# led-strip-main-connector.net
KiCad netlist of a schematic drawn in EAGLE
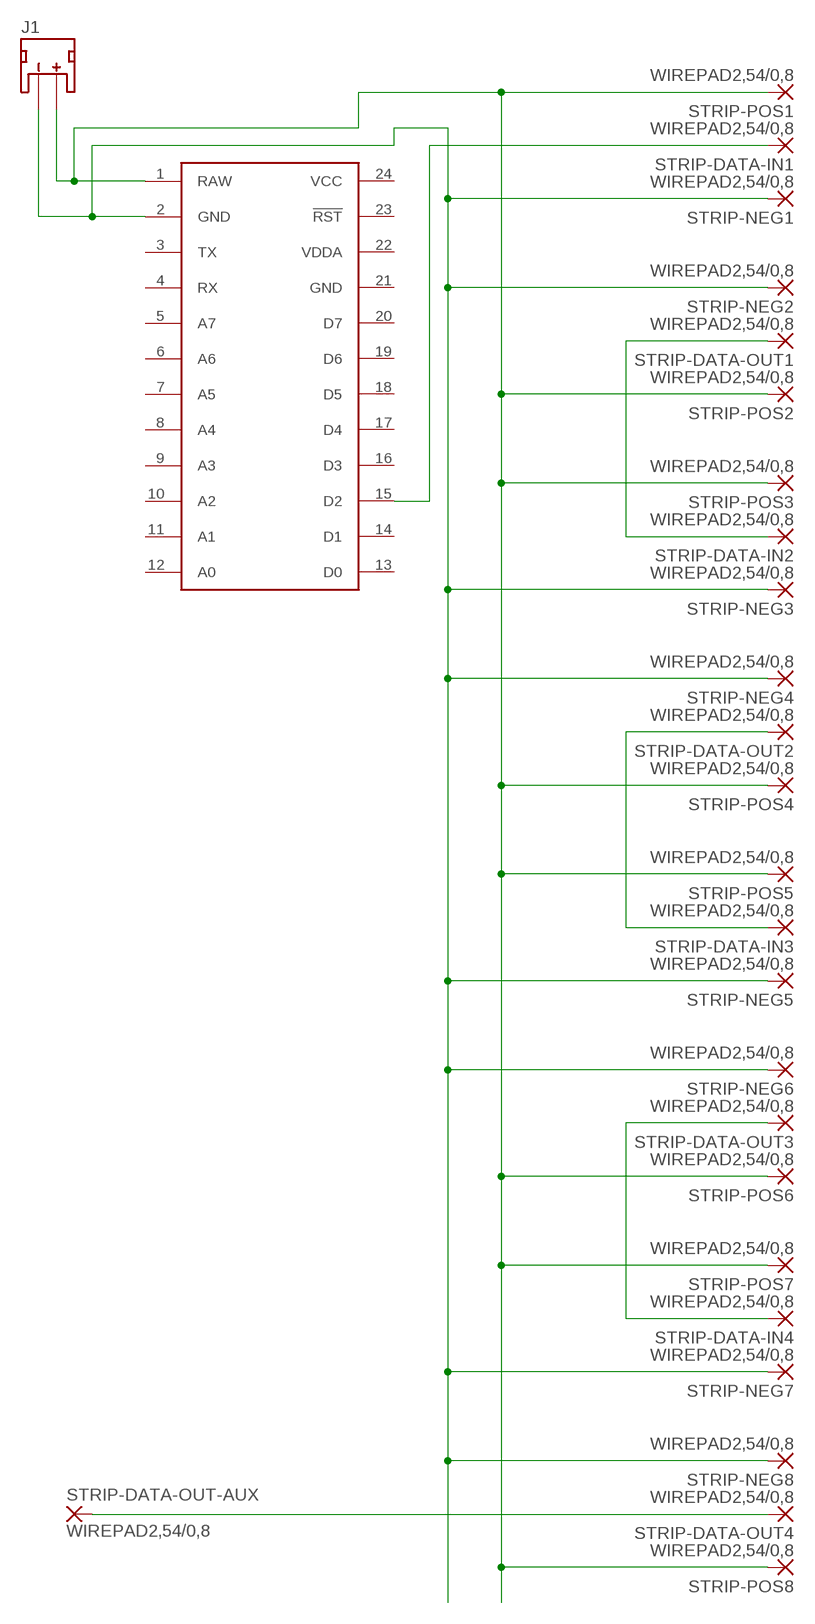
[diagram p0: schematic, sheet 1]

(export (version "E")
  (design (tool "Eeschema 10.0.6"))
  (components
    (comp (ref "J1")
      (value "1")
      (footprint "eagle-import:JST-2-SMD")
      (libsource (lib "eagle-import") (part "JST_2MM_MALE"))
    )
    (comp (ref "SPARK_CORE")
      (value "SPARK_CORECORE")
      (footprint "eagle-import:SPARK_CORE")
      (libsource (lib "eagle-import") (part "SPARK_CORECORE"))
    )
    (comp (ref "STRIP-DATA-IN1")
      (value "WIREPAD2,54/0,8")
      (footprint "eagle-import:2,54_0,8")
      (libsource (lib "eagle-import") (part "WIREPAD2,54/0,8"))
    )
    (comp (ref "STRIP-DATA-IN2")
      (value "WIREPAD2,54/0,8")
      (footprint "eagle-import:2,54_0,8")
      (libsource (lib "eagle-import") (part "WIREPAD2,54/0,8"))
    )
    (comp (ref "STRIP-DATA-IN3")
      (value "WIREPAD2,54/0,8")
      (footprint "eagle-import:2,54_0,8")
      (libsource (lib "eagle-import") (part "WIREPAD2,54/0,8"))
    )
    (comp (ref "STRIP-DATA-IN4")
      (value "WIREPAD2,54/0,8")
      (footprint "eagle-import:2,54_0,8")
      (libsource (lib "eagle-import") (part "WIREPAD2,54/0,8"))
    )
    (comp (ref "STRIP-DATA-OUT-AUX")
      (value "WIREPAD2,54/0,8")
      (footprint "eagle-import:2,54_0,8")
      (libsource (lib "eagle-import") (part "WIREPAD2,54/0,8"))
    )
    (comp (ref "STRIP-DATA-OUT1")
      (value "WIREPAD2,54/0,8")
      (footprint "eagle-import:2,54_0,8")
      (libsource (lib "eagle-import") (part "WIREPAD2,54/0,8"))
    )
    (comp (ref "STRIP-DATA-OUT2")
      (value "WIREPAD2,54/0,8")
      (footprint "eagle-import:2,54_0,8")
      (libsource (lib "eagle-import") (part "WIREPAD2,54/0,8"))
    )
    (comp (ref "STRIP-DATA-OUT3")
      (value "WIREPAD2,54/0,8")
      (footprint "eagle-import:2,54_0,8")
      (libsource (lib "eagle-import") (part "WIREPAD2,54/0,8"))
    )
    (comp (ref "STRIP-DATA-OUT4")
      (value "WIREPAD2,54/0,8")
      (footprint "eagle-import:2,54_0,8")
      (libsource (lib "eagle-import") (part "WIREPAD2,54/0,8"))
    )
    (comp (ref "STRIP-NEG1")
      (value "WIREPAD2,54/0,8")
      (footprint "eagle-import:2,54_0,8")
      (libsource (lib "eagle-import") (part "WIREPAD2,54/0,8"))
    )
    (comp (ref "STRIP-NEG2")
      (value "WIREPAD2,54/0,8")
      (footprint "eagle-import:2,54_0,8")
      (libsource (lib "eagle-import") (part "WIREPAD2,54/0,8"))
    )
    (comp (ref "STRIP-NEG3")
      (value "WIREPAD2,54/0,8")
      (footprint "eagle-import:2,54_0,8")
      (libsource (lib "eagle-import") (part "WIREPAD2,54/0,8"))
    )
    (comp (ref "STRIP-NEG4")
      (value "WIREPAD2,54/0,8")
      (footprint "eagle-import:2,54_0,8")
      (libsource (lib "eagle-import") (part "WIREPAD2,54/0,8"))
    )
    (comp (ref "STRIP-NEG5")
      (value "WIREPAD2,54/0,8")
      (footprint "eagle-import:2,54_0,8")
      (libsource (lib "eagle-import") (part "WIREPAD2,54/0,8"))
    )
    (comp (ref "STRIP-NEG6")
      (value "WIREPAD2,54/0,8")
      (footprint "eagle-import:2,54_0,8")
      (libsource (lib "eagle-import") (part "WIREPAD2,54/0,8"))
    )
    (comp (ref "STRIP-NEG7")
      (value "WIREPAD2,54/0,8")
      (footprint "eagle-import:2,54_0,8")
      (libsource (lib "eagle-import") (part "WIREPAD2,54/0,8"))
    )
    (comp (ref "STRIP-NEG8")
      (value "WIREPAD2,54/0,8")
      (footprint "eagle-import:2,54_0,8")
      (libsource (lib "eagle-import") (part "WIREPAD2,54/0,8"))
    )
    (comp (ref "STRIP-POS1")
      (value "WIREPAD2,54/0,8")
      (footprint "eagle-import:2,54_0,8")
      (libsource (lib "eagle-import") (part "WIREPAD2,54/0,8"))
    )
    (comp (ref "STRIP-POS2")
      (value "WIREPAD2,54/0,8")
      (footprint "eagle-import:2,54_0,8")
      (libsource (lib "eagle-import") (part "WIREPAD2,54/0,8"))
    )
    (comp (ref "STRIP-POS3")
      (value "WIREPAD2,54/0,8")
      (footprint "eagle-import:2,54_0,8")
      (libsource (lib "eagle-import") (part "WIREPAD2,54/0,8"))
    )
    (comp (ref "STRIP-POS4")
      (value "WIREPAD2,54/0,8")
      (footprint "eagle-import:2,54_0,8")
      (libsource (lib "eagle-import") (part "WIREPAD2,54/0,8"))
    )
    (comp (ref "STRIP-POS5")
      (value "WIREPAD2,54/0,8")
      (footprint "eagle-import:2,54_0,8")
      (libsource (lib "eagle-import") (part "WIREPAD2,54/0,8"))
    )
    (comp (ref "STRIP-POS6")
      (value "WIREPAD2,54/0,8")
      (footprint "eagle-import:2,54_0,8")
      (libsource (lib "eagle-import") (part "WIREPAD2,54/0,8"))
    )
    (comp (ref "STRIP-POS7")
      (value "WIREPAD2,54/0,8")
      (footprint "eagle-import:2,54_0,8")
      (libsource (lib "eagle-import") (part "WIREPAD2,54/0,8"))
    )
    (comp (ref "STRIP-POS8")
      (value "WIREPAD2,54/0,8")
      (footprint "eagle-import:2,54_0,8")
      (libsource (lib "eagle-import") (part "WIREPAD2,54/0,8"))
    )
  )
  (nets
    (net (code "1") (name "/GND") (class "Default")
      (node (ref "SPARK_CORE") (pin "21") (pinfunction "GND_21") (pintype "power_in"))
    )
    (net (code "2") (name "/VCC") (class "Default")
      (node (ref "SPARK_CORE") (pin "24") (pinfunction "VCC_24") (pintype "power_in"))
    )
    (net (code "3") (name "/VDDA") (class "Default")
      (node (ref "SPARK_CORE") (pin "22") (pinfunction "VDDA_22") (pintype "power_in"))
    )
    (net (code "4") (name "Net-(J1-+)") (class "Default")
      (node (ref "J1") (pin "2") (pinfunction "+_2") (pintype "bidirectional"))
      (node (ref "SPARK_CORE") (pin "1") (pinfunction "RAW_1") (pintype "power_in"))
      (node (ref "STRIP-POS1") (pin "1") (pinfunction "P_1") (pintype "passive"))
      (node (ref "STRIP-POS2") (pin "1") (pinfunction "P_1") (pintype "passive"))
      (node (ref "STRIP-POS3") (pin "1") (pinfunction "P_1") (pintype "passive"))
      (node (ref "STRIP-POS4") (pin "1") (pinfunction "P_1") (pintype "passive"))
      (node (ref "STRIP-POS5") (pin "1") (pinfunction "P_1") (pintype "passive"))
      (node (ref "STRIP-POS6") (pin "1") (pinfunction "P_1") (pintype "passive"))
      (node (ref "STRIP-POS7") (pin "1") (pinfunction "P_1") (pintype "passive"))
      (node (ref "STRIP-POS8") (pin "1") (pinfunction "P_1") (pintype "passive"))
    )
    (net (code "5") (name "Net-(J1--)") (class "Default")
      (node (ref "J1") (pin "1") (pinfunction "-_1") (pintype "bidirectional"))
      (node (ref "SPARK_CORE") (pin "2") (pinfunction "GND_2") (pintype "power_in"))
      (node (ref "STRIP-NEG1") (pin "1") (pinfunction "P_1") (pintype "passive"))
      (node (ref "STRIP-NEG2") (pin "1") (pinfunction "P_1") (pintype "passive"))
      (node (ref "STRIP-NEG3") (pin "1") (pinfunction "P_1") (pintype "passive"))
      (node (ref "STRIP-NEG4") (pin "1") (pinfunction "P_1") (pintype "passive"))
      (node (ref "STRIP-NEG5") (pin "1") (pinfunction "P_1") (pintype "passive"))
      (node (ref "STRIP-NEG6") (pin "1") (pinfunction "P_1") (pintype "passive"))
      (node (ref "STRIP-NEG7") (pin "1") (pinfunction "P_1") (pintype "passive"))
      (node (ref "STRIP-NEG8") (pin "1") (pinfunction "P_1") (pintype "passive"))
    )
    (net (code "6") (name "Net-(SPARK_CORE-D2)") (class "Default")
      (node (ref "SPARK_CORE") (pin "15") (pinfunction "D2_15") (pintype "bidirectional"))
      (node (ref "STRIP-DATA-IN1") (pin "1") (pinfunction "P_1") (pintype "passive"))
    )
    (net (code "7") (name "Net-(STRIP-DATA-IN2-P)") (class "Default")
      (node (ref "STRIP-DATA-IN2") (pin "1") (pinfunction "P_1") (pintype "passive"))
      (node (ref "STRIP-DATA-OUT1") (pin "1") (pinfunction "P_1") (pintype "passive"))
    )
    (net (code "8") (name "Net-(STRIP-DATA-IN3-P)") (class "Default")
      (node (ref "STRIP-DATA-IN3") (pin "1") (pinfunction "P_1") (pintype "passive"))
      (node (ref "STRIP-DATA-OUT2") (pin "1") (pinfunction "P_1") (pintype "passive"))
    )
    (net (code "9") (name "Net-(STRIP-DATA-IN4-P)") (class "Default")
      (node (ref "STRIP-DATA-IN4") (pin "1") (pinfunction "P_1") (pintype "passive"))
      (node (ref "STRIP-DATA-OUT3") (pin "1") (pinfunction "P_1") (pintype "passive"))
    )
    (net (code "10") (name "Net-(STRIP-DATA-OUT-AUX-P)") (class "Default")
      (node (ref "STRIP-DATA-OUT-AUX") (pin "1") (pinfunction "P_1") (pintype "passive"))
      (node (ref "STRIP-DATA-OUT4") (pin "1") (pinfunction "P_1") (pintype "passive"))
    )
    (net (code "11") (name "unconnected-(J1-PAD1-PadNC1)") (class "Default")
      (node (ref "J1") (pin "NC1") (pinfunction "PAD1_NC1") (pintype "bidirectional"))
    )
    (net (code "12") (name "unconnected-(J1-PAD2-PadNC2)") (class "Default")
      (node (ref "J1") (pin "NC2") (pinfunction "PAD2_NC2") (pintype "bidirectional"))
    )
    (net (code "13") (name "unconnected-(SPARK_CORE-A0-Pad12)") (class "Default")
      (node (ref "SPARK_CORE") (pin "12") (pinfunction "A0_12") (pintype "bidirectional"))
    )
    (net (code "14") (name "unconnected-(SPARK_CORE-A1-Pad11)") (class "Default")
      (node (ref "SPARK_CORE") (pin "11") (pinfunction "A1_11") (pintype "bidirectional"))
    )
    (net (code "15") (name "unconnected-(SPARK_CORE-A2-Pad10)") (class "Default")
      (node (ref "SPARK_CORE") (pin "10") (pinfunction "A2_10") (pintype "bidirectional"))
    )
    (net (code "16") (name "unconnected-(SPARK_CORE-A3-Pad9)") (class "Default")
      (node (ref "SPARK_CORE") (pin "9") (pinfunction "A3_9") (pintype "bidirectional"))
    )
    (net (code "17") (name "unconnected-(SPARK_CORE-A4-Pad8)") (class "Default")
      (node (ref "SPARK_CORE") (pin "8") (pinfunction "A4_8") (pintype "bidirectional"))
    )
    (net (code "18") (name "unconnected-(SPARK_CORE-A5-Pad7)") (class "Default")
      (node (ref "SPARK_CORE") (pin "7") (pinfunction "A5_7") (pintype "bidirectional"))
    )
    (net (code "19") (name "unconnected-(SPARK_CORE-A6-Pad6)") (class "Default")
      (node (ref "SPARK_CORE") (pin "6") (pinfunction "A6_6") (pintype "bidirectional"))
    )
    (net (code "20") (name "unconnected-(SPARK_CORE-A7-Pad5)") (class "Default")
      (node (ref "SPARK_CORE") (pin "5") (pinfunction "A7_5") (pintype "bidirectional"))
    )
    (net (code "21") (name "unconnected-(SPARK_CORE-D0-Pad13)") (class "Default")
      (node (ref "SPARK_CORE") (pin "13") (pinfunction "D0_13") (pintype "bidirectional"))
    )
    (net (code "22") (name "unconnected-(SPARK_CORE-D1-Pad14)") (class "Default")
      (node (ref "SPARK_CORE") (pin "14") (pinfunction "D1_14") (pintype "bidirectional"))
    )
    (net (code "23") (name "unconnected-(SPARK_CORE-D3-Pad16)") (class "Default")
      (node (ref "SPARK_CORE") (pin "16") (pinfunction "D3_16") (pintype "bidirectional"))
    )
    (net (code "24") (name "unconnected-(SPARK_CORE-D4-Pad17)") (class "Default")
      (node (ref "SPARK_CORE") (pin "17") (pinfunction "D4_17") (pintype "bidirectional"))
    )
    (net (code "25") (name "unconnected-(SPARK_CORE-D5-Pad18)") (class "Default")
      (node (ref "SPARK_CORE") (pin "18") (pinfunction "D5_18") (pintype "bidirectional"))
    )
    (net (code "26") (name "unconnected-(SPARK_CORE-D6-Pad19)") (class "Default")
      (node (ref "SPARK_CORE") (pin "19") (pinfunction "D6_19") (pintype "bidirectional"))
    )
    (net (code "27") (name "unconnected-(SPARK_CORE-D7-Pad20)") (class "Default")
      (node (ref "SPARK_CORE") (pin "20") (pinfunction "D7_20") (pintype "bidirectional"))
    )
    (net (code "28") (name "unconnected-(SPARK_CORE-RX-Pad4)") (class "Default")
      (node (ref "SPARK_CORE") (pin "4") (pinfunction "RX_4") (pintype "bidirectional"))
    )
    (net (code "29") (name "unconnected-(SPARK_CORE-TX-Pad3)") (class "Default")
      (node (ref "SPARK_CORE") (pin "3") (pinfunction "TX_3") (pintype "bidirectional"))
    )
    (net (code "30") (name "unconnected-(SPARK_CORE-~{RST}-Pad23)") (class "Default")
      (node (ref "SPARK_CORE") (pin "23") (pinfunction "~{RST}_23") (pintype "bidirectional"))
    )
  )
)
